# sata-3_3v-injector.net
KiCad netlist of a schematic drawn in EasyEDA Pro
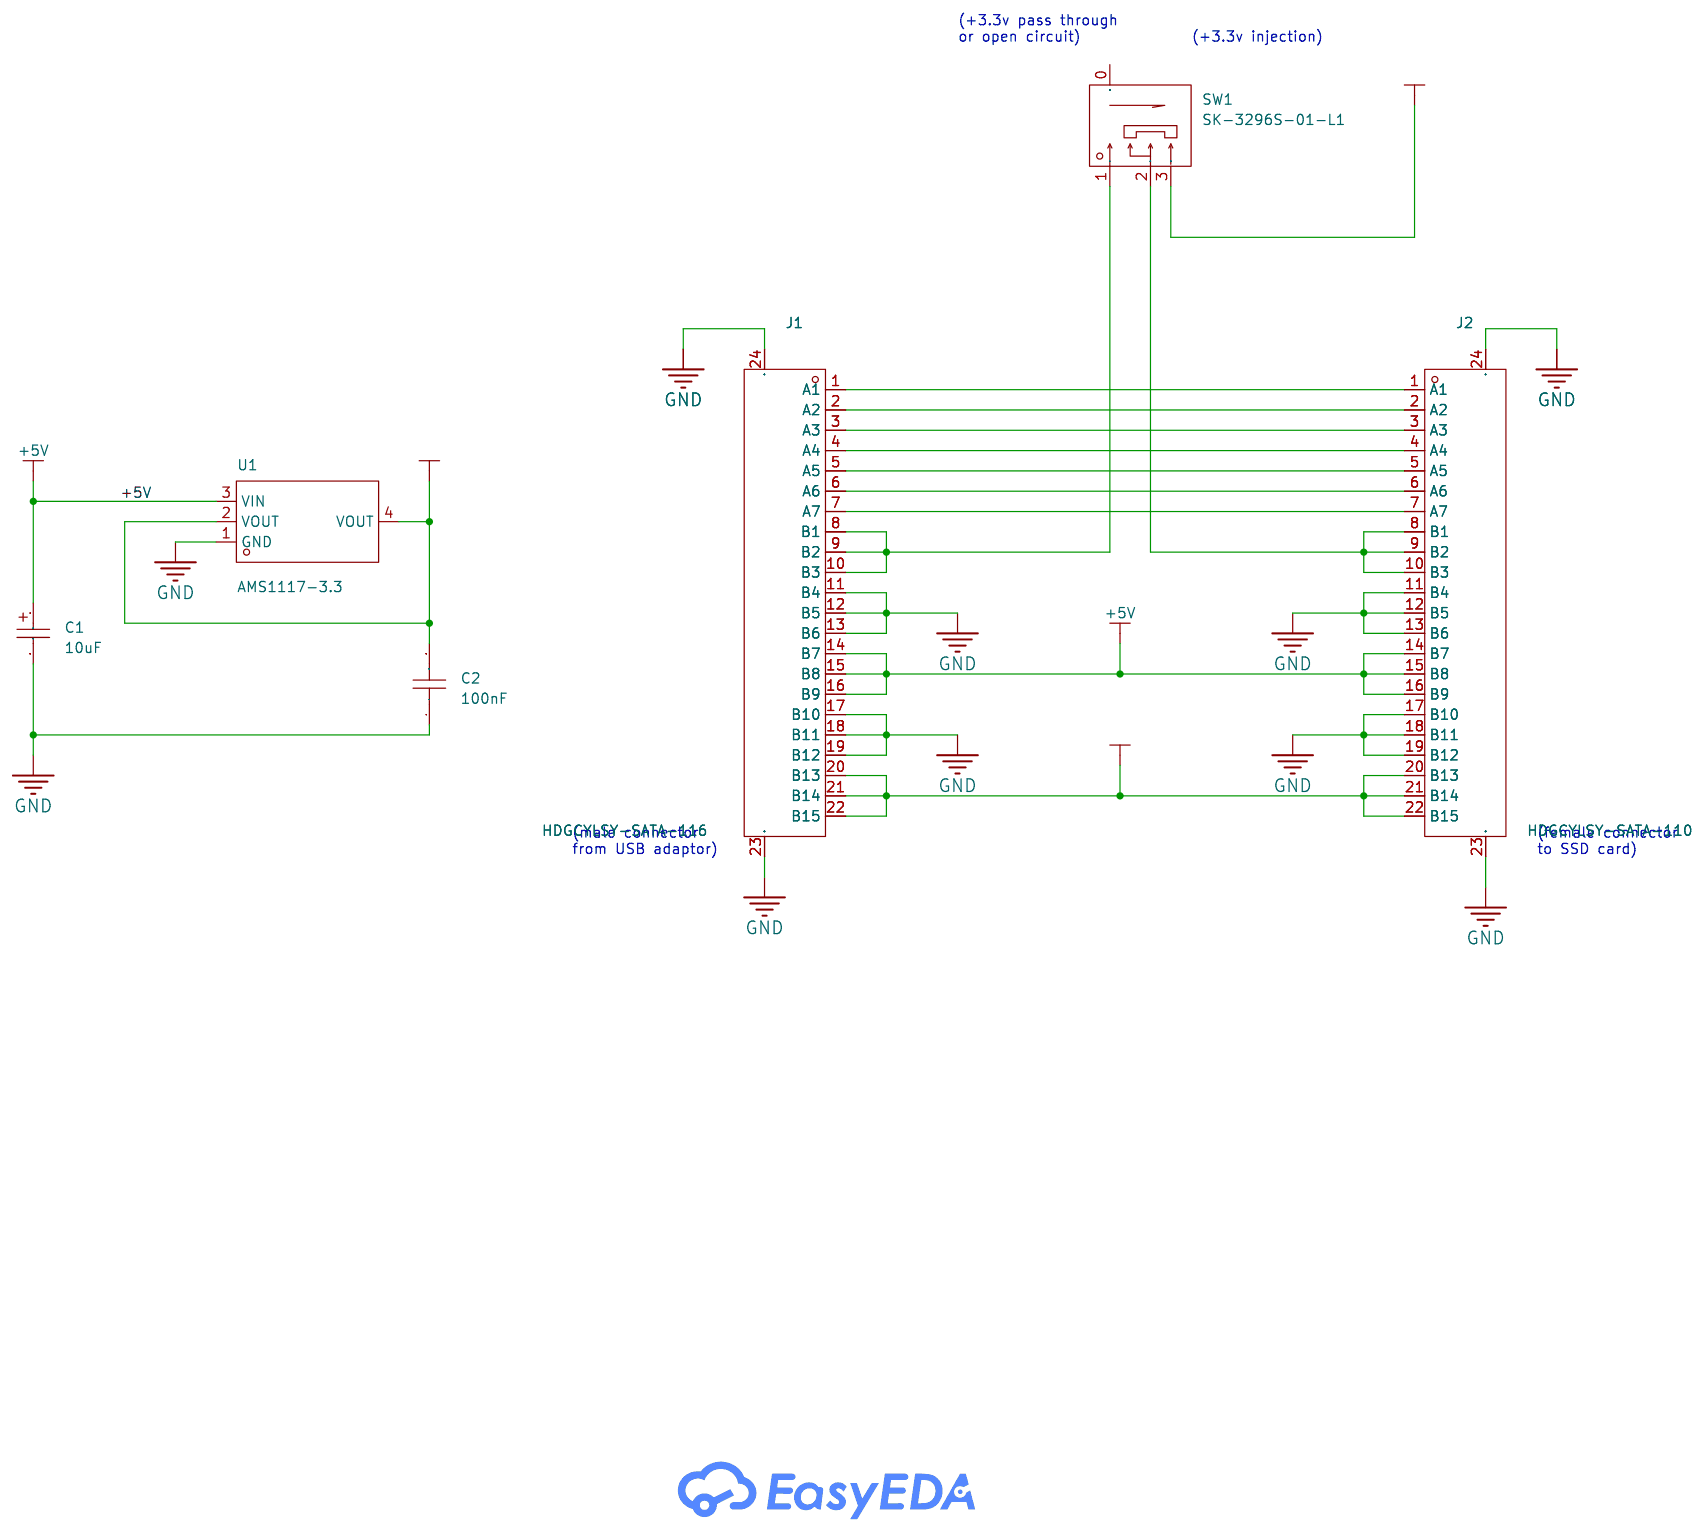
[diagram p0: schematic sheet]

(export (version "E")
  (design (tool "Eeschema 10.0.6"))
  (components
    (comp (ref "C1")
      (value "10uF")
      (footprint "easyedapro:CAP-SMD_L3.2-W1.6-RD-C7171")
      (fields (field (name "Manufacturer Part") "TAJA106K016RNJ") (field (name "Manufacturer") "Kyocera AVX"))
      (libsource (lib "easyedapro") (part "TAJA106K016RNJ"))
    )
    (comp (ref "C2")
      (value "100nF")
      (footprint "easyedapro:C1206")
      (fields
        (field (name "Manufacturer Part") "GCM31C5C1H104JA16L")
        (field (name "Manufacturer") "muRata(村田)")
      )
      (libsource (lib "easyedapro") (part "GCM31C5C1H104JA16L"))
    )
    (comp (ref "J1")
      (value "HDGCYLSY-SATA-116")
      (footprint "easyedapro:CONN-SMD_HDGCYLSY-SATA-116")
      (fields (field (name "Manufacturer") "HDGC(华德共创)"))
      (libsource (lib "easyedapro") (part "HDGCYLSY-SATA-116"))
    )
    (comp (ref "J2")
      (value "HDGCYLSY-SATA-110")
      (footprint "easyedapro:CONN-TH_HDGCYLSY-SATA-110")
      (fields (field (name "Manufacturer") "HDGC(华德共创)"))
      (libsource (lib "easyedapro") (part "HDGCYLSY-SATA-110"))
    )
    (comp (ref "SW1")
      (value "SK-3296S-01-L1")
      (footprint "easyedapro:SW-SMD_3P-P1.50_L2.7-W6.6")
      (fields (field (name "Manufacturer") "XKB Connectivity(中国星坤)"))
      (libsource (lib "easyedapro") (part "SK-3296S-01-L1"))
    )
    (comp (ref "U1")
      (value "AMS1117-3.3")
      (footprint "easyedapro:SOT-223-3_L6.5-W3.4-P2.30-LS7.0-BR")
      (fields (field (name "Manufacturer") "AMS"))
      (libsource (lib "easyedapro") (part "AMS1117-3.3"))
    )
  )
  (nets
    (net (code "1") (name "+3V3") (class "Default")
      (node (ref "C2") (pin "2") (pinfunction "2_2") (pintype "unspecified"))
      (node (ref "SW1") (pin "3") (pinfunction "3_3") (pintype "unspecified"))
      (node (ref "U1") (pin "2") (pinfunction "VOUT_2") (pintype "unspecified"))
      (node (ref "U1") (pin "4") (pinfunction "VOUT_4") (pintype "unspecified"))
    )
    (net (code "2") (name "+5V") (class "Default")
      (node (ref "C1") (pin "1") (pinfunction "1_1") (pintype "input"))
      (node (ref "J1") (pin "14") (pinfunction "B7_14") (pintype "unspecified"))
      (node (ref "J1") (pin "15") (pinfunction "B8_15") (pintype "unspecified"))
      (node (ref "J1") (pin "16") (pinfunction "B9_16") (pintype "unspecified"))
      (node (ref "J2") (pin "14") (pinfunction "B7_14") (pintype "unspecified"))
      (node (ref "J2") (pin "15") (pinfunction "B8_15") (pintype "unspecified"))
      (node (ref "J2") (pin "16") (pinfunction "B9_16") (pintype "unspecified"))
      (node (ref "U1") (pin "3") (pinfunction "VIN_3") (pintype "unspecified"))
    )
    (net (code "3") (name "+12V") (class "Default")
      (node (ref "J1") (pin "20") (pinfunction "B13_20") (pintype "unspecified"))
      (node (ref "J1") (pin "21") (pinfunction "B14_21") (pintype "unspecified"))
      (node (ref "J1") (pin "22") (pinfunction "B15_22") (pintype "unspecified"))
      (node (ref "J2") (pin "20") (pinfunction "B13_20") (pintype "unspecified"))
      (node (ref "J2") (pin "21") (pinfunction "B14_21") (pintype "unspecified"))
      (node (ref "J2") (pin "22") (pinfunction "B15_22") (pintype "unspecified"))
    )
    (net (code "4") (name "GND") (class "Default")
      (node (ref "C1") (pin "2") (pinfunction "2_2") (pintype "input"))
      (node (ref "C2") (pin "1") (pinfunction "1_1") (pintype "unspecified"))
      (node (ref "J1") (pin "11") (pinfunction "B4_11") (pintype "unspecified"))
      (node (ref "J1") (pin "12") (pinfunction "B5_12") (pintype "unspecified"))
      (node (ref "J1") (pin "13") (pinfunction "B6_13") (pintype "unspecified"))
      (node (ref "J1") (pin "17") (pinfunction "B10_17") (pintype "unspecified"))
      (node (ref "J1") (pin "18") (pinfunction "B11_18") (pintype "unspecified"))
      (node (ref "J1") (pin "19") (pinfunction "B12_19") (pintype "unspecified"))
      (node (ref "J1") (pin "23") (pinfunction "23_23") (pintype "unspecified"))
      (node (ref "J1") (pin "24") (pinfunction "24_24") (pintype "unspecified"))
      (node (ref "J2") (pin "11") (pinfunction "B4_11") (pintype "unspecified"))
      (node (ref "J2") (pin "12") (pinfunction "B5_12") (pintype "unspecified"))
      (node (ref "J2") (pin "13") (pinfunction "B6_13") (pintype "unspecified"))
      (node (ref "J2") (pin "17") (pinfunction "B10_17") (pintype "unspecified"))
      (node (ref "J2") (pin "18") (pinfunction "B11_18") (pintype "unspecified"))
      (node (ref "J2") (pin "19") (pinfunction "B12_19") (pintype "unspecified"))
      (node (ref "J2") (pin "23") (pinfunction "23_23") (pintype "unspecified"))
      (node (ref "J2") (pin "24") (pinfunction "24_24") (pintype "unspecified"))
      (node (ref "U1") (pin "1") (pinfunction "GND_1") (pintype "unspecified"))
    )
    (net (code "5") (name "Net-(J1-A1)") (class "Default")
      (node (ref "J1") (pin "1") (pinfunction "A1_1") (pintype "unspecified"))
      (node (ref "J2") (pin "1") (pinfunction "A1_1") (pintype "unspecified"))
    )
    (net (code "6") (name "Net-(J1-A2)") (class "Default")
      (node (ref "J1") (pin "2") (pinfunction "A2_2") (pintype "unspecified"))
      (node (ref "J2") (pin "2") (pinfunction "A2_2") (pintype "unspecified"))
    )
    (net (code "7") (name "Net-(J1-A3)") (class "Default")
      (node (ref "J1") (pin "3") (pinfunction "A3_3") (pintype "unspecified"))
      (node (ref "J2") (pin "3") (pinfunction "A3_3") (pintype "unspecified"))
    )
    (net (code "8") (name "Net-(J1-A4)") (class "Default")
      (node (ref "J1") (pin "4") (pinfunction "A4_4") (pintype "unspecified"))
      (node (ref "J2") (pin "4") (pinfunction "A4_4") (pintype "unspecified"))
    )
    (net (code "9") (name "Net-(J1-A5)") (class "Default")
      (node (ref "J1") (pin "5") (pinfunction "A5_5") (pintype "unspecified"))
      (node (ref "J2") (pin "5") (pinfunction "A5_5") (pintype "unspecified"))
    )
    (net (code "10") (name "Net-(J1-A6)") (class "Default")
      (node (ref "J1") (pin "6") (pinfunction "A6_6") (pintype "unspecified"))
      (node (ref "J2") (pin "6") (pinfunction "A6_6") (pintype "unspecified"))
    )
    (net (code "11") (name "Net-(J1-A7)") (class "Default")
      (node (ref "J1") (pin "7") (pinfunction "A7_7") (pintype "unspecified"))
      (node (ref "J2") (pin "7") (pinfunction "A7_7") (pintype "unspecified"))
    )
    (net (code "12") (name "Net-(J1-B1)") (class "Default")
      (node (ref "J1") (pin "10") (pinfunction "B3_10") (pintype "unspecified"))
      (node (ref "J1") (pin "8") (pinfunction "B1_8") (pintype "unspecified"))
      (node (ref "J1") (pin "9") (pinfunction "B2_9") (pintype "unspecified"))
      (node (ref "SW1") (pin "1") (pinfunction "1_1") (pintype "unspecified"))
    )
    (net (code "13") (name "Net-(J2-B1)") (class "Default")
      (node (ref "J2") (pin "10") (pinfunction "B3_10") (pintype "unspecified"))
      (node (ref "J2") (pin "8") (pinfunction "B1_8") (pintype "unspecified"))
      (node (ref "J2") (pin "9") (pinfunction "B2_9") (pintype "unspecified"))
      (node (ref "SW1") (pin "2") (pinfunction "2_2") (pintype "unspecified"))
    )
    (net (code "14") (name "unconnected-(SW1-Pad0)") (class "Default")
      (node (ref "SW1") (pin "0") (pinfunction "0_0") (pintype "unspecified"))
    )
  )
)
